# ComandosExt.net
KiCad netlist of a schematic drawn in Altium Designer
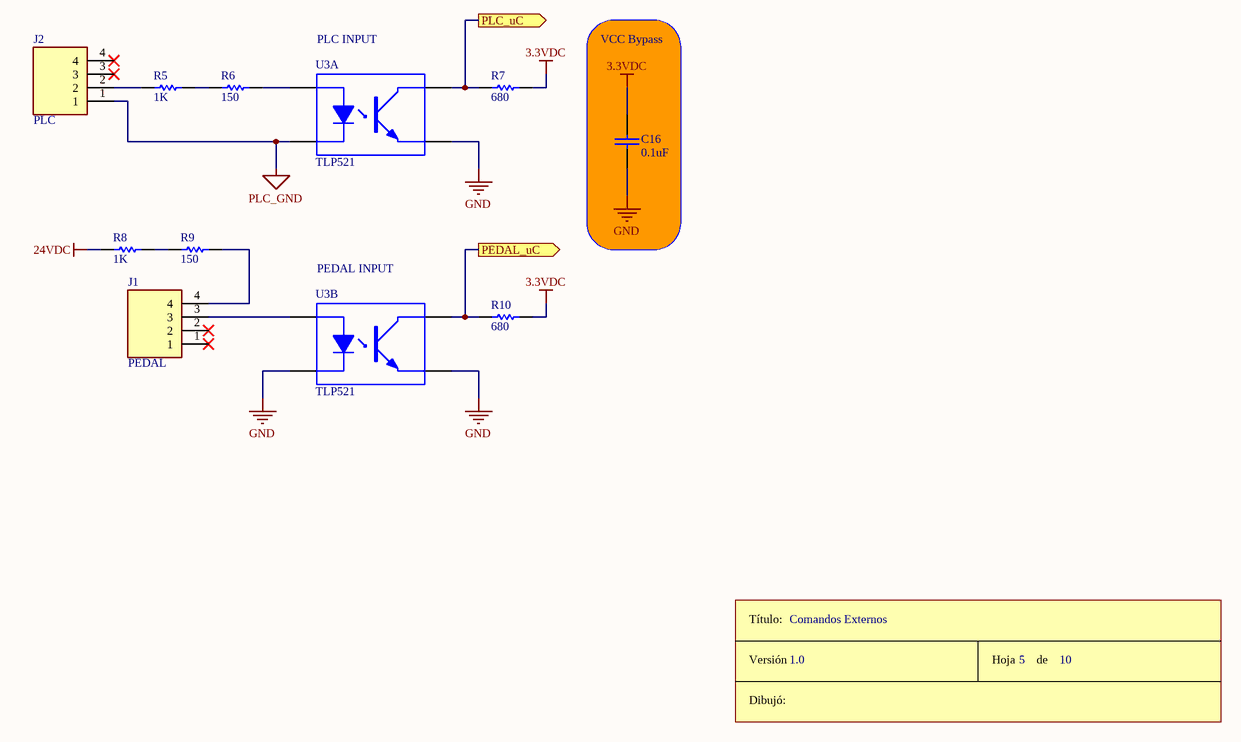
[diagram p0: ComandosExt.SchDoc]

(export (version "E")
  (design (tool "Eeschema 10.0.6"))
  (components
    (comp (ref "C16") (value "0.1uF") (footprint "CAP100") (libsource (lib "LIBEBAL") (part "CAP")))
    (comp (ref "J1")
      (value "PEDAL")
      (footprint "TE_1586863-4")
      (description "Conn Power HDR 4 POS 4.2mm Solder RA Thru-Hole 4 Terminal 1 Port Tray")
      (fields (field (name "MF") "TE Connectivity") (field (name "MP") "1586863-4"))
      (libsource (lib "MFW4R") (part "1586863-4"))
    )
    (comp (ref "J2")
      (value "PLC")
      (footprint "TE_1586863-4")
      (description "Conn Power HDR 4 POS 4.2mm Solder RA Thru-Hole 4 Terminal 1 Port Tray")
      (fields (field (name "MF") "TE Connectivity") (field (name "MP") "1586863-4"))
      (libsource (lib "MFW4R") (part "1586863-4"))
    )
    (comp (ref "R5") (value "1K") (footprint "RES300") (libsource (lib "LIBEBAL") (part "RES")))
    (comp (ref "R6") (value "150") (footprint "RES300") (libsource (lib "LIBEBAL") (part "RES")))
    (comp (ref "R7") (value "680") (footprint "RES300") (libsource (lib "LIBEBAL") (part "RES")))
    (comp (ref "R8") (value "1K") (footprint "RES300") (libsource (lib "LIBEBAL") (part "RES")))
    (comp (ref "R9") (value "150") (footprint "RES300") (libsource (lib "LIBEBAL") (part "RES")))
    (comp (ref "R10") (value "680") (footprint "RES300") (libsource (lib "LIBEBAL") (part "RES")))
    (comp (ref "ROT3") (value "Rótulo") (libsource (lib "LIB PIO IX") (part "Rótulo")))
    (comp (ref "U3")
      (value "TLP521")
      (footprint "DIP8")
      (description "PhotoCoupler")
      (libsource (lib "AditionalComponents") (part "TLP521-2"))
    )
  )
  (nets
    (net (code "1") (name "/PEDAL_uC") (class "Default")
      (node (ref "R10") (pin "1") (pinfunction "1_1") (pintype "passive"))
      (node (ref "U3") (pin "6") (pinfunction "C_6") (pintype "passive"))
    )
    (net (code "2") (name "/PLC_uC") (class "Default")
      (node (ref "R7") (pin "1") (pinfunction "1_1") (pintype "passive"))
      (node (ref "U3") (pin "8") (pinfunction "C_8") (pintype "passive"))
    )
    (net (code "3") (name "3.3VDC") (class "Default")
      (node (ref "C16") (pin "1") (pinfunction "1_1") (pintype "passive"))
      (node (ref "R10") (pin "2") (pinfunction "2_2") (pintype "passive"))
      (node (ref "R7") (pin "2") (pinfunction "2_2") (pintype "passive"))
    )
    (net (code "4") (name "24VDC") (class "Default")
      (node (ref "R8") (pin "1") (pinfunction "1_1") (pintype "passive"))
    )
    (net (code "5") (name "GND") (class "Default")
      (node (ref "C16") (pin "2") (pinfunction "2_2") (pintype "passive"))
      (node (ref "U3") (pin "4") (pinfunction "K_4") (pintype "passive"))
      (node (ref "U3") (pin "5") (pinfunction "E_5") (pintype "passive"))
      (node (ref "U3") (pin "7") (pinfunction "E_7") (pintype "passive"))
    )
    (net (code "6") (name "Net-(J1-Pad4)") (class "Default")
      (node (ref "J1") (pin "4") (pinfunction "4_4") (pintype "passive"))
      (node (ref "R9") (pin "2") (pinfunction "2_2") (pintype "passive"))
    )
    (net (code "7") (name "Net-(J2-Pad2)") (class "Default")
      (node (ref "J2") (pin "2") (pinfunction "2_2") (pintype "passive"))
      (node (ref "R5") (pin "1") (pinfunction "1_1") (pintype "passive"))
    )
    (net (code "8") (name "Net-(R5-Pad2)") (class "Default")
      (node (ref "R5") (pin "2") (pinfunction "2_2") (pintype "passive"))
      (node (ref "R6") (pin "1") (pinfunction "1_1") (pintype "passive"))
    )
    (net (code "9") (name "Net-(R8-Pad2)") (class "Default")
      (node (ref "R8") (pin "2") (pinfunction "2_2") (pintype "passive"))
      (node (ref "R9") (pin "1") (pinfunction "1_1") (pintype "passive"))
    )
    (net (code "10") (name "Net-(U3A-A)") (class "Default")
      (node (ref "R6") (pin "2") (pinfunction "2_2") (pintype "passive"))
      (node (ref "U3") (pin "1") (pinfunction "A_1") (pintype "passive"))
    )
    (net (code "11") (name "Net-(U3B-A)") (class "Default")
      (node (ref "J1") (pin "3") (pinfunction "3_3") (pintype "passive"))
      (node (ref "U3") (pin "3") (pinfunction "A_3") (pintype "passive"))
    )
    (net (code "12") (name "PLC_GND") (class "Default")
      (node (ref "J2") (pin "1") (pinfunction "1_1") (pintype "passive"))
      (node (ref "U3") (pin "2") (pinfunction "K_2") (pintype "passive"))
    )
    (net (code "13") (name "unconnected-(J1-Pad1)") (class "Default")
      (node (ref "J1") (pin "1") (pinfunction "1_1") (pintype "passive+no_connect"))
    )
    (net (code "14") (name "unconnected-(J1-Pad2)") (class "Default")
      (node (ref "J1") (pin "2") (pinfunction "2_2") (pintype "passive+no_connect"))
    )
    (net (code "15") (name "unconnected-(J2-Pad3)") (class "Default")
      (node (ref "J2") (pin "3") (pinfunction "3_3") (pintype "passive+no_connect"))
    )
    (net (code "16") (name "unconnected-(J2-Pad4)") (class "Default")
      (node (ref "J2") (pin "4") (pinfunction "4_4") (pintype "passive+no_connect"))
    )
  )
)
